# 00_POWER.net
KiCad netlist of a schematic drawn in Altium Designer
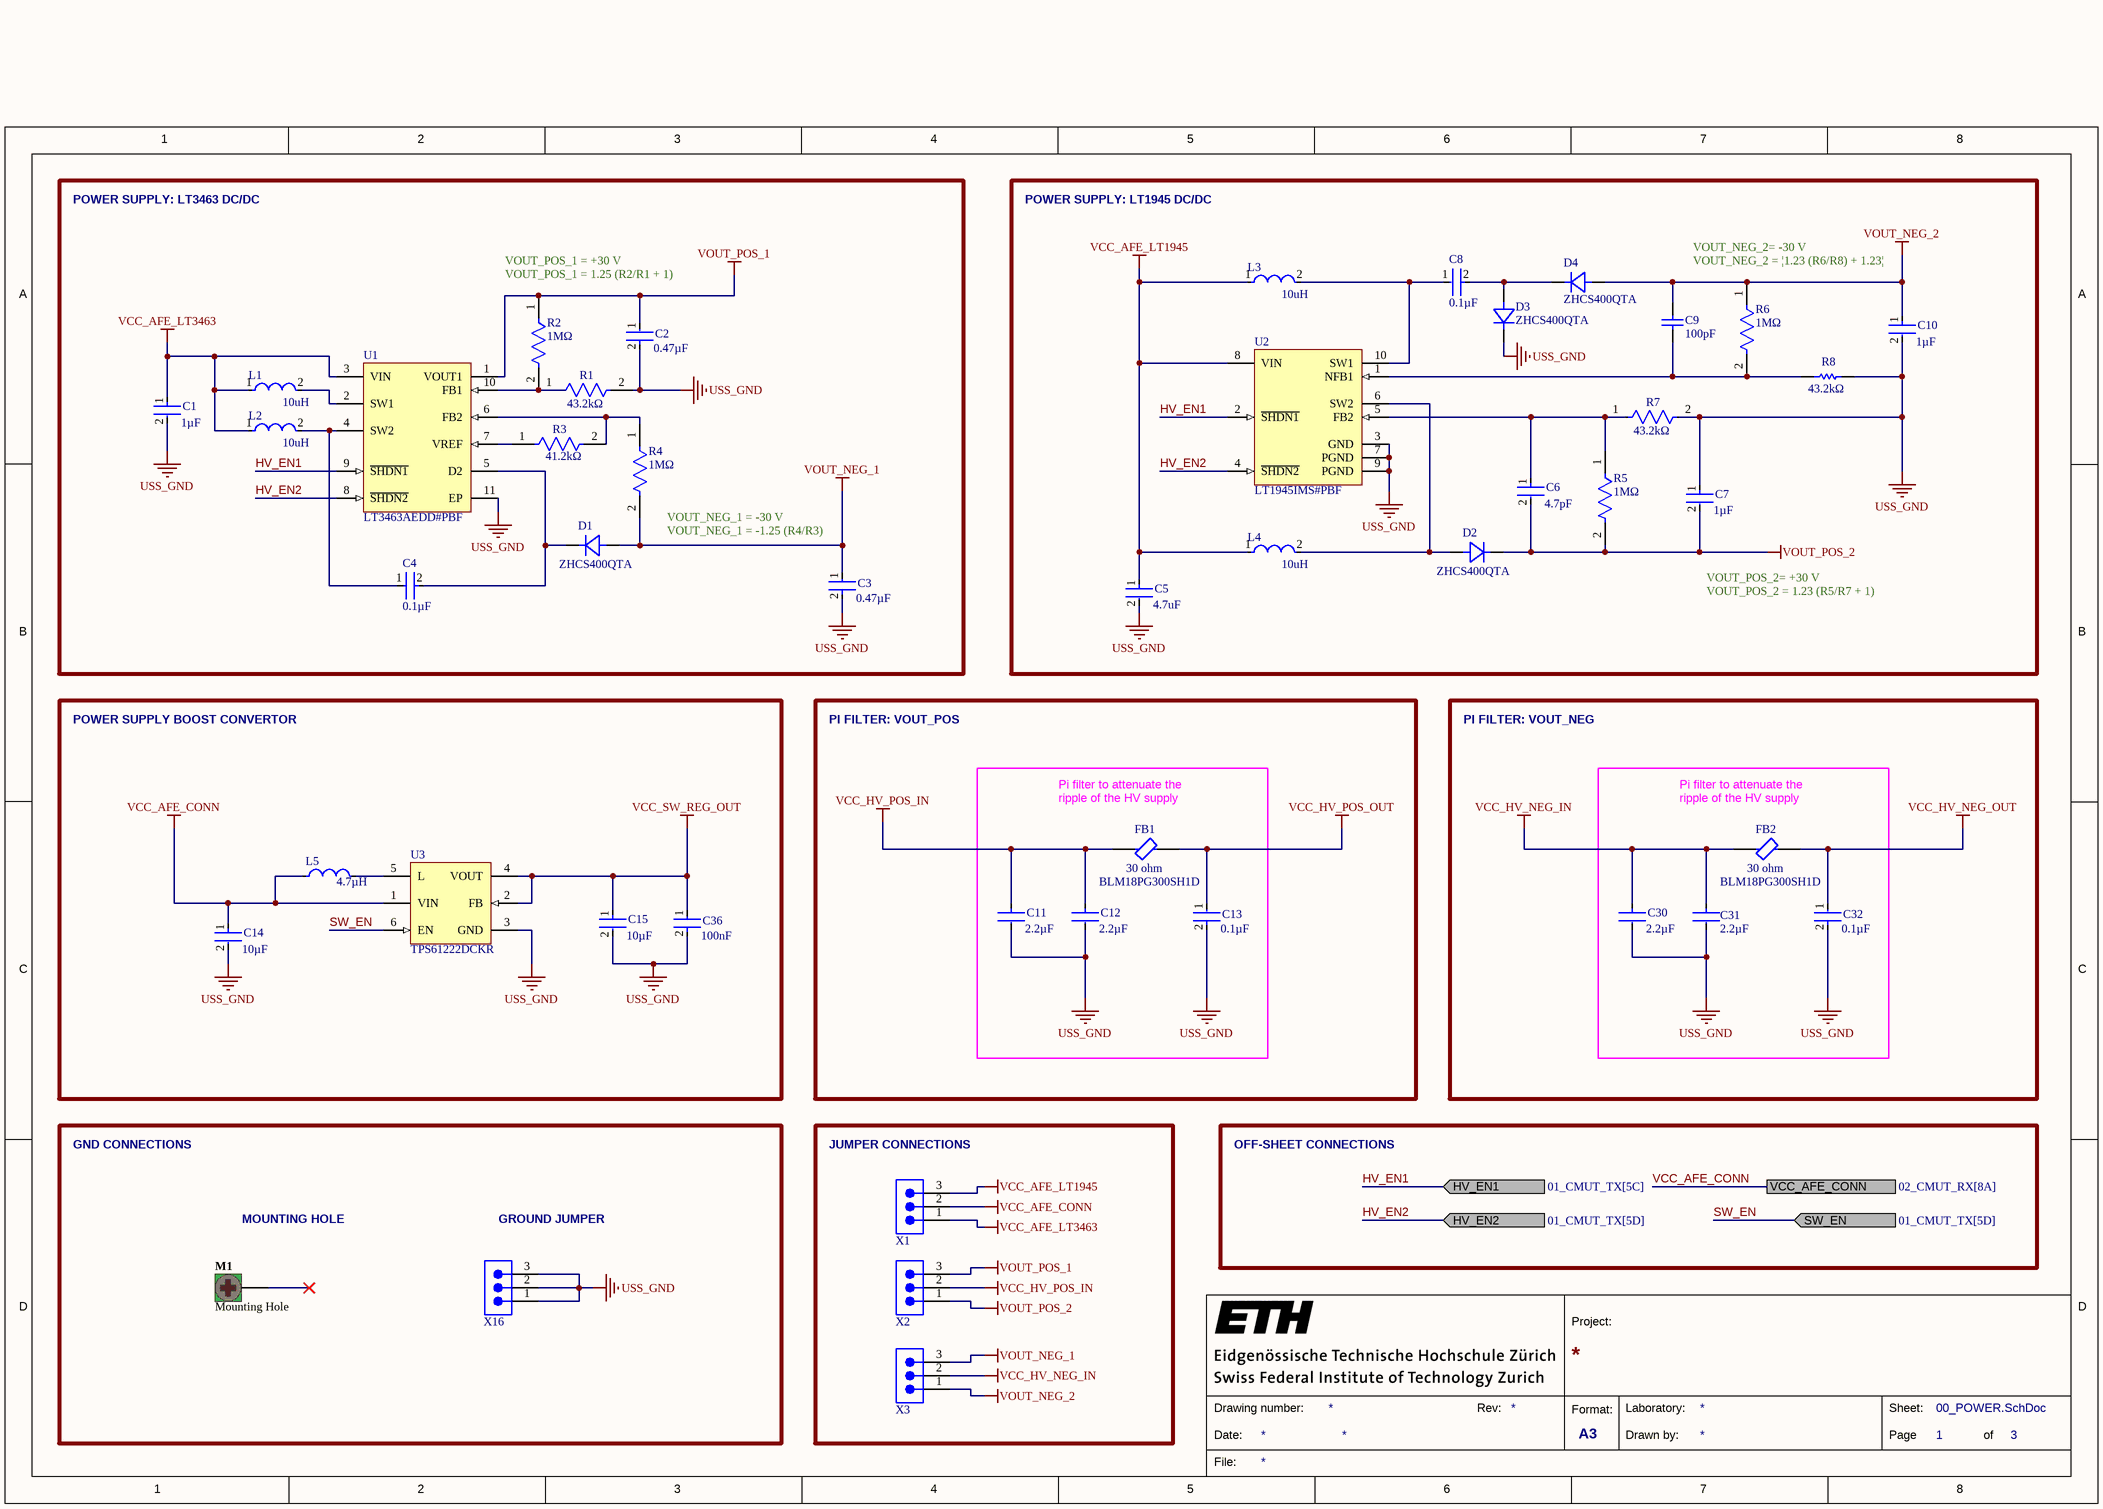
[diagram p0: 00_POWER.SchDoc]

(export (version "E")
  (design (tool "Eeschema 10.0.6"))
  (components
    (comp (ref "C1")
      (value "CGA3E3X5R1H105K")
      (footprint "FP-CGA3E-0_3-0_1-IPC_B")
      (description "Cap Ceramic 1uF 50V X5R 10% Pad SMD 0603 +85°C Automotive T/R")
      (fields (field (name "TOLERANCE") "10%") (field (name "CAPACITANCE") "1µF"))
      (libsource (lib "Altium Content Vault") (part "b4654b650e69147ec39a6b967a45e02"))
    )
    (comp (ref "C2")
      (value "C1608X5R1H474K080AB")
      (footprint "FP-C1608-080-0_1-IPC_C")
      (description "Multilayer Ceramic Capacitors 470nF ±10% 50V X5R SMD 0603")
      (fields
        (field (name "VOLTAGE") "50V")
        (field (name "TOLERANCE") "10%")
        (field (name "CAPACITANCE") "0.47µF")
      )
      (libsource (lib "Altium Content Vault") (part "236180d848d6139a670b325ea6854c9"))
    )
    (comp (ref "C3")
      (value "C1608X5R1H474K080AB")
      (footprint "FP-C1608-080-0_1-IPC_C")
      (description "Multilayer Ceramic Capacitors 470nF ±10% 50V X5R SMD 0603")
      (fields
        (field (name "VOLTAGE") "50V")
        (field (name "TOLERANCE") "10%")
        (field (name "CAPACITANCE") "0.47µF")
      )
      (libsource (lib "Altium Content Vault") (part "236180d848d6139a670b325ea6854c9"))
    )
    (comp (ref "C4")
      (value "C1608X5R1H104K080AA")
      (footprint "FP-C1608-080-0_1-MFG")
      (description "Multilayer Ceramic Capacitors 100nF ±10% 50V X5R SMD 0603")
      (fields (field (name "TOLERANCE") "10%") (field (name "CAPACITANCE") "0.1µF"))
      (libsource (lib "Altium Content Vault") (part "236180d848d6139a670b325ea6854c9"))
    )
    (comp (ref "C5")
      (value "C1608X5R1V475K080AC")
      (footprint "FP-C1608-080-0_2-MFG")
      (description "CAP CER 4.7UF 35V X5R 0603")
      (fields (field (name "CAPACITANCE") "4.7uF") (field (name "TOLERANCE") "10%"))
      (libsource (lib "Altium Content Vault") (part "02cd4be3c70576c341d710602a673aa"))
    )
    (comp (ref "C6")
      (value "C0603C479K5GAC7867")
      (footprint "FP-C0603C-CF-MFG")
      (description "CAP CER 4.7PF 50V NP0 0603")
      (fields
        (field (name "OCTOPART") "https://octopart.com/c0603c479k5gac7867-kemet-2009260")
        (field (name "MANUFACTURER") "KEMET")
        (field (name "CAPACITANCE") "4.7pF")
      )
      (libsource (lib "Altium Content Vault") (part "b4654b650e69147ec39a6b967a45e02"))
    )
    (comp (ref "C7")
      (value "CGA3E3X5R1H105K")
      (footprint "FP-CGA3E-0_3-0_1-IPC_B")
      (description "Cap Ceramic 1uF 50V X5R 10% Pad SMD 0603 +85°C Automotive T/R")
      (fields (field (name "TOLERANCE") "10%") (field (name "CAPACITANCE") "1µF"))
      (libsource (lib "Altium Content Vault") (part "b4654b650e69147ec39a6b967a45e02"))
    )
    (comp (ref "C8")
      (value "C1608X5R1H104K080AA")
      (footprint "FP-C1608-080-0_1-MFG")
      (description "Multilayer Ceramic Capacitors 100nF ±10% 50V X5R SMD 0603")
      (fields (field (name "TOLERANCE") "10%") (field (name "CAPACITANCE") "0.1µF"))
      (libsource (lib "Altium Content Vault") (part "236180d848d6139a670b325ea6854c9"))
    )
    (comp (ref "C9")
      (value "06035C101KAT2A")
      (footprint "CAPC1608X90X35LL15T15")
      (fields (field (name "MANUFACTURER") "AVX Interconnect / Elco") (field (name "CAPACITANCE") "100pF"))
      (libsource (lib "Altium Content Vault") (part "CAP"))
    )
    (comp (ref "C10")
      (value "CGA3E3X5R1H105K")
      (footprint "FP-CGA3E-0_3-0_1-IPC_B")
      (description "Cap Ceramic 1uF 50V X5R 10% Pad SMD 0603 +85°C Automotive T/R")
      (fields (field (name "TOLERANCE") "10%") (field (name "CAPACITANCE") "1µF"))
      (libsource (lib "Altium Content Vault") (part "b4654b650e69147ec39a6b967a45e02"))
    )
    (comp (ref "C11")
      (value "GRM188R61H225KE11D")
      (footprint "FP-GRM188-0_2-IPC_C")
      (description "Chip Multilayer Ceramic Capacitors for General Purpose, 0603, 2.2uF, X5R, 15%, 10%, 50V")
      (fields (field (name "TOLERANCE") "10%") (field (name "CAPACITANCE") "2.2µF"))
      (libsource (lib "Altium Content Vault") (part "11868f565c42a9108669ba33697ecf6"))
    )
    (comp (ref "C12")
      (value "GRM188R61H225KE11D")
      (footprint "FP-GRM188-0_2-IPC_C")
      (description "Chip Multilayer Ceramic Capacitors for General Purpose, 0603, 2.2uF, X5R, 15%, 10%, 50V")
      (fields (field (name "TOLERANCE") "10%") (field (name "CAPACITANCE") "2.2µF"))
      (libsource (lib "Altium Content Vault") (part "11868f565c42a9108669ba33697ecf6"))
    )
    (comp (ref "C13")
      (value "C1608X5R1H104K080AA")
      (footprint "FP-C1608-080-0_1-MFG")
      (description "Multilayer Ceramic Capacitors 100nF ±10% 50V X5R SMD 0603")
      (fields (field (name "TOLERANCE") "10%") (field (name "CAPACITANCE") "0.1µF"))
      (libsource (lib "Altium Content Vault") (part "236180d848d6139a670b325ea6854c9"))
    )
    (comp (ref "C14")
      (value "GRM188R6YA106MA73D")
      (footprint "FP-GRM188-0_2-IPC_C")
      (description "Chip Multilayer Ceramic Capacitors for General Purpose, 0603, 10uF, X5R, 15%, 20%, 35V")
      (fields (field (name "CAPACITANCE") "10µF") (field (name "TOLERANCE") "20%"))
      (libsource (lib "") (part "11868f565c42a9108669ba33697ecf6_1"))
    )
    (comp (ref "C15")
      (value "GRM188R6YA106MA73D")
      (footprint "FP-GRM188-0_2-IPC_C")
      (description "Chip Multilayer Ceramic Capacitors for General Purpose, 0603, 10uF, X5R, 15%, 20%, 35V")
      (fields (field (name "CAPACITANCE") "10µF") (field (name "TOLERANCE") "20%"))
      (libsource (lib "") (part "11868f565c42a9108669ba33697ecf6_1"))
    )
    (comp (ref "C30")
      (value "GRM188R61H225KE11D")
      (footprint "FP-GRM188-0_2-IPC_C")
      (description "Chip Multilayer Ceramic Capacitors for General Purpose, 0603, 2.2uF, X5R, 15%, 10%, 50V")
      (fields (field (name "TOLERANCE") "10%") (field (name "CAPACITANCE") "2.2µF"))
      (libsource (lib "Altium Content Vault") (part "11868f565c42a9108669ba33697ecf6"))
    )
    (comp (ref "C31")
      (value "Murata GRM188R61H225KE11D")
      (footprint "FP-GRM188-0_2-IPC_C")
      (description "Chip Multilayer Ceramic Capacitors for General Purpose, 0603, 2.2uF, X5R, 15%, 10%, 50V")
      (fields (field (name "TOLERANCE") "10%") (field (name "CAPACITANCE") "2.2µF"))
      (libsource (lib "Altium Content Vault") (part "11868f565c42a9108669ba33697ecf6"))
    )
    (comp (ref "C32")
      (value "C1608X5R1H104K080AA")
      (footprint "FP-C1608-080-0_1-MFG")
      (description "Multilayer Ceramic Capacitors 100nF ±10% 50V X5R SMD 0603")
      (fields (field (name "TOLERANCE") "10%") (field (name "CAPACITANCE") "0.1µF"))
      (libsource (lib "Altium Content Vault") (part "236180d848d6139a670b325ea6854c9"))
    )
    (comp (ref "C36")
      (value "C1608X5R1H104K080AA")
      (footprint "FP-C1608-080-0_1-MFG")
      (description "Multilayer Ceramic Capacitors 100nF ±10% 50V X5R SMD 0603")
      (fields (field (name "TOLERANCE") "10%") (field (name "CAPACITANCE") "100nF"))
      (libsource (lib "Altium Content Vault") (part "236180d848d6139a670b325ea6854c9"))
    )
    (comp (ref "D1")
      (value "ZHCS400QTA")
      (footprint "DIODE_SOD323_DIO")
      (description "Diode Schottky 40V 1A Automotive 2-Pin SOD-323 T/R")
      (fields (field (name "MANUFACTURER") "Diodes"))
      (libsource (lib "Schlib1") (part "ZHCS400QTA"))
    )
    (comp (ref "D2")
      (value "ZHCS400QTA")
      (footprint "DIODE_SOD323_DIO")
      (description "Diode Schottky 40V 1A Automotive 2-Pin SOD-323 T/R")
      (fields (field (name "MANUFACTURER") "Diodes"))
      (libsource (lib "Schlib1") (part "ZHCS400QTA"))
    )
    (comp (ref "D3")
      (value "ZHCS400QTA")
      (footprint "DIODE_SOD323_DIO")
      (description "Diode Schottky 40V 1A Automotive 2-Pin SOD-323 T/R")
      (fields (field (name "MANUFACTURER") "Diodes"))
      (libsource (lib "Schlib1") (part "ZHCS400QTA"))
    )
    (comp (ref "D4")
      (value "ZHCS400QTA")
      (footprint "DIODE_SOD323_DIO")
      (description "Diode Schottky 40V 1A Automotive 2-Pin SOD-323 T/R")
      (fields (field (name "MANUFACTURER") "Diodes"))
      (libsource (lib "Schlib1") (part "ZHCS400QTA"))
    )
    (comp (ref "FB1")
      (value "BLM18PG300SH1D")
      (footprint "FP-BLM18-0_15-t0_8-IPC_A")
      (description "Chip Ferrite Bead, 0603, 30Ω @ 100MHz, 0.05Ω, , 1A")
      (fields (field (name "IMPEDANCE") "30 ohm") (field (name "TOLERANCE") "25%"))
      (libsource (lib "Altium Content Vault") (part "5f30dd21d616792df468990f7003faa"))
    )
    (comp (ref "FB2")
      (value "BLM18PG300SH1D")
      (footprint "FP-BLM18-0_15-t0_8-IPC_A")
      (description "Chip Ferrite Bead, 0603, 30Ω @ 100MHz, 0.05Ω, , 1A")
      (fields (field (name "IMPEDANCE") "30 ohm") (field (name "TOLERANCE") "25%"))
      (libsource (lib "Altium Content Vault") (part "5f30dd21d616792df468990f7003faa"))
    )
    (comp (ref "L1")
      (value "B82422A1103K100")
      (footprint "FP-B82422A-MFG")
      (description "FIXED IND 10UH 180MA 1.6 OHM SMD")
      (fields (field (name "INDUCTANCE") "10uH") (field (name "TOLERANCE") "10%"))
      (libsource (lib "") (part "725321dda6339637d4d059423bc1c3c_1"))
    )
    (comp (ref "L2")
      (value "B82422A1103K100")
      (footprint "FP-B82422A-MFG")
      (description "FIXED IND 10UH 180MA 1.6 OHM SMD")
      (fields (field (name "INDUCTANCE") "10uH") (field (name "TOLERANCE") "10%"))
      (libsource (lib "") (part "725321dda6339637d4d059423bc1c3c_1"))
    )
    (comp (ref "L3")
      (value "B82422A1103K100")
      (footprint "FP-B82422A-MFG")
      (description "FIXED IND 10UH 180MA 1.6 OHM SMD")
      (fields (field (name "INDUCTANCE") "10uH") (field (name "TOLERANCE") "10%"))
      (libsource (lib "") (part "725321dda6339637d4d059423bc1c3c_1"))
    )
    (comp (ref "L4")
      (value "B82422A1103K100")
      (footprint "FP-B82422A-MFG")
      (description "FIXED IND 10UH 180MA 1.6 OHM SMD")
      (fields (field (name "INDUCTANCE") "10uH") (field (name "TOLERANCE") "10%"))
      (libsource (lib "") (part "725321dda6339637d4d059423bc1c3c_1"))
    )
    (comp (ref "L5")
      (value "NR3012T4R7M")
      (footprint "FP-NR3012-MFG")
      (description "SMD Power Inductors 4.7uH ±20% 0.77A 0.13Ω")
      (fields (field (name "TOLERANCE") "20%") (field (name "INDUCTANCE") "4.7µH"))
      (libsource (lib "Altium Content Vault") (part "725321dda6339637d4d059423bc1c3c"))
    )
    (comp (ref "M1")
      (value "Mounting Hole")
      (footprint "Mounting Hole")
      (description "M2 Hole, 2.4mm drill, 5mm landing pads, 3mm pad in middle layers, no overlay")
      (libsource (lib "ETHZ Vault") (part "Hole"))
    )
    (comp (ref "R1")
      (value "RC0603FR-0743K2L")
      (footprint "FP-RC0603-0_55-MFG")
      (description "RES SMD 43.2K OHM 1% 1/10W 0603")
      (fields (field (name "TOLERANCE") "1%") (field (name "RESISTANCE") "43.2kΩ"))
      (libsource (lib "Altium Content Vault") (part "1029c3af85768c4190bb7ad29bc67b5"))
    )
    (comp (ref "R2")
      (value "RC0603JR-071ML")
      (footprint "FP-RC0603-0_55-IPC_C")
      (description "RES SMD 1M OHM 5% 1/10W 0603")
      (fields (field (name "TOLERANCE") "5%") (field (name "RESISTANCE") "1MΩ"))
      (libsource (lib "Altium Content Vault") (part "1029c3af85768c4190bb7ad29bc67b5"))
    )
    (comp (ref "R3")
      (value "RK73H1JTTDD4122D")
      (footprint "FP-RK73H1J-IPC_A")
      (description "41.2kΩ ±0.5% 0.1W Chip Resistor 0603 Thick Film AEC-Q200 Qualified")
      (fields (field (name "RESISTANCE") "41.2kΩ") (field (name "TOLERANCE") "0.5%"))
      (libsource (lib "Altium Content Vault") (part "1029c3af85768c4190bb7ad29bc67b5"))
    )
    (comp (ref "R4")
      (value "RC0603JR-071ML")
      (footprint "FP-RC0603-0_55-IPC_C")
      (description "RES SMD 1M OHM 5% 1/10W 0603")
      (fields (field (name "TOLERANCE") "5%") (field (name "RESISTANCE") "1MΩ"))
      (libsource (lib "Altium Content Vault") (part "1029c3af85768c4190bb7ad29bc67b5"))
    )
    (comp (ref "R5")
      (value "RC0603JR-071ML")
      (footprint "FP-RC0603-0_55-IPC_C")
      (description "RES SMD 1M OHM 5% 1/10W 0603")
      (fields (field (name "TOLERANCE") "5%") (field (name "RESISTANCE") "1MΩ"))
      (libsource (lib "Altium Content Vault") (part "1029c3af85768c4190bb7ad29bc67b5"))
    )
    (comp (ref "R6")
      (value "RC0603JR-071ML")
      (footprint "FP-RC0603-0_55-IPC_C")
      (description "RES SMD 1M OHM 5% 1/10W 0603")
      (fields (field (name "TOLERANCE") "5%") (field (name "RESISTANCE") "1MΩ"))
      (libsource (lib "Altium Content Vault") (part "1029c3af85768c4190bb7ad29bc67b5"))
    )
    (comp (ref "R7")
      (value "RC0603FR-0743K2L")
      (footprint "FP-RC0603-0_55-MFG")
      (description "RES SMD 43.2K OHM 1% 1/10W 0603")
      (fields (field (name "TOLERANCE") "1%") (field (name "RESISTANCE") "43.2kΩ"))
      (libsource (lib "Altium Content Vault") (part "1029c3af85768c4190bb7ad29bc67b5"))
    )
    (comp (ref "R8")
      (value "RK73H1JTTD4322F")
      (footprint "RESC1608X55X30ML20T10")
      (fields (field (name "MANUFACTURER") "KOA Speer") (field (name "RESISTANCE") "43.2kΩ"))
      (libsource (lib "Altium Content Vault") (part "RES"))
    )
    (comp (ref "U1")
      (value "LT3463AEDD#PBF")
      (footprint "LT-DD-10_V")
      (fields (field (name "MANUFACTURER") "Linear Technology"))
      (libsource (lib "Altium Content Vault") (part "LT-LT3463A-DD-10"))
    )
    (comp (ref "U2")
      (value "LT1945IMS#PBF")
      (footprint "LT-MS-10_L")
      (fields (field (name "MANUFACTURER") "Linear Technology"))
      (libsource (lib "Altium Content Vault") (part "LT-LT1945-MS-10"))
    )
    (comp (ref "U3")
      (value "TPS61222DCKR")
      (footprint "DCK0006A_L")
      (fields (field (name "MANUFACTURER") "Texas Instruments"))
      (libsource (lib "Altium Content Vault") (part "TI-TPS61222DCK6"))
    )
    (comp (ref "X1")
      (value "68000-103HLF")
      (footprint "68000-103HLF")
      (description "3 Positions Header, Unshrouded Connector 0.100\" (2.54mm) Through Hole Gold or Gold, GXT™")
      (fields (field (name "MANUFACTURER") "Amphenol FCI"))
      (libsource (lib "ETHZ Vault") (part "CON-1x3-Male"))
    )
    (comp (ref "X2")
      (value "68000-103HLF")
      (footprint "68000-103HLF")
      (description "3 Positions Header, Unshrouded Connector 0.100\" (2.54mm) Through Hole Gold or Gold, GXT™")
      (fields (field (name "MANUFACTURER") "Amphenol FCI"))
      (libsource (lib "ETHZ Vault") (part "CON-1x3-Male"))
    )
    (comp (ref "X3")
      (value "68000-103HLF")
      (footprint "68000-103HLF")
      (description "3 Positions Header, Unshrouded Connector 0.100\" (2.54mm) Through Hole Gold or Gold, GXT™")
      (fields (field (name "MANUFACTURER") "Amphenol FCI"))
      (libsource (lib "ETHZ Vault") (part "CON-1x3-Male"))
    )
    (comp (ref "X16")
      (value "68000-103HLF")
      (footprint "68000-103HLF")
      (description "3 Positions Header, Unshrouded Connector 0.100\" (2.54mm) Through Hole Gold or Gold, GXT™")
      (fields (field (name "MANUFACTURER") "Amphenol FCI"))
      (libsource (lib "ETHZ Vault") (part "CON-1x3-Male"))
    )
  )
  (nets
    (net (code "1") (name "/HV_EN1") (class "Default")
      (node (ref "U1") (pin "9") (pinfunction "~{SHDN1}_9") (pintype "input"))
      (node (ref "U2") (pin "2") (pinfunction "~{SHDN1}_2") (pintype "input"))
    )
    (net (code "2") (name "/HV_EN2") (class "Default")
      (node (ref "U1") (pin "8") (pinfunction "~{SHDN2}_8") (pintype "input"))
      (node (ref "U2") (pin "4") (pinfunction "~{SHDN2}_4") (pintype "input"))
    )
    (net (code "3") (name "/SW_EN") (class "Default")
      (node (ref "U3") (pin "6") (pinfunction "EN_6") (pintype "input"))
    )
    (net (code "4") (name "Net-(C8-Pad2)") (class "Default")
      (node (ref "C8") (pin "2") (pinfunction "2_2") (pintype "passive"))
      (node (ref "D3") (pin "2") (pinfunction "2_2") (pintype "passive"))
      (node (ref "D4") (pin "1") (pinfunction "1_1") (pintype "passive"))
    )
    (net (code "5") (name "Net-(U1-D2)") (class "Default")
      (node (ref "C4") (pin "2") (pinfunction "2_2") (pintype "passive"))
      (node (ref "D1") (pin "1") (pinfunction "1_1") (pintype "passive"))
      (node (ref "U1") (pin "5") (pinfunction "D2_5") (pintype "passive"))
    )
    (net (code "6") (name "Net-(U1-FB1)") (class "Default")
      (node (ref "R1") (pin "1") (pinfunction "1_1") (pintype "passive"))
      (node (ref "R2") (pin "2") (pinfunction "2_2") (pintype "passive"))
      (node (ref "U1") (pin "10") (pinfunction "FB1_10") (pintype "input"))
    )
    (net (code "7") (name "Net-(U1-FB2)") (class "Default")
      (node (ref "R3") (pin "2") (pinfunction "2_2") (pintype "passive"))
      (node (ref "R4") (pin "1") (pinfunction "1_1") (pintype "passive"))
      (node (ref "U1") (pin "6") (pinfunction "FB2_6") (pintype "input"))
    )
    (net (code "8") (name "Net-(U1-SW1)") (class "Default")
      (node (ref "L1") (pin "2") (pinfunction "2_2") (pintype "passive"))
      (node (ref "U1") (pin "2") (pinfunction "SW1_2") (pintype "passive"))
    )
    (net (code "9") (name "Net-(U1-SW2)") (class "Default")
      (node (ref "C4") (pin "1") (pinfunction "1_1") (pintype "passive"))
      (node (ref "L2") (pin "2") (pinfunction "2_2") (pintype "passive"))
      (node (ref "U1") (pin "4") (pinfunction "SW2_4") (pintype "passive"))
    )
    (net (code "10") (name "Net-(U1-VREF)") (class "Default")
      (node (ref "R3") (pin "1") (pinfunction "1_1") (pintype "passive"))
      (node (ref "U1") (pin "7") (pinfunction "VREF_7") (pintype "input"))
    )
    (net (code "11") (name "Net-(U2-FB2)") (class "Default")
      (node (ref "C6") (pin "1") (pinfunction "1_1") (pintype "passive"))
      (node (ref "R5") (pin "1") (pinfunction "1_1") (pintype "passive"))
      (node (ref "R7") (pin "1") (pinfunction "1_1") (pintype "passive"))
      (node (ref "U2") (pin "5") (pinfunction "FB2_5") (pintype "input"))
    )
    (net (code "12") (name "Net-(U2-NFB1)") (class "Default")
      (node (ref "C9") (pin "1") (pinfunction "1_1") (pintype "passive"))
      (node (ref "R6") (pin "2") (pinfunction "2_2") (pintype "passive"))
      (node (ref "R8") (pin "1") (pinfunction "1_1") (pintype "passive"))
      (node (ref "U2") (pin "1") (pinfunction "NFB1_1") (pintype "input"))
    )
    (net (code "13") (name "Net-(U2-SW1)") (class "Default")
      (node (ref "C8") (pin "1") (pinfunction "1_1") (pintype "passive"))
      (node (ref "L3") (pin "2") (pinfunction "2_2") (pintype "passive"))
      (node (ref "U2") (pin "10") (pinfunction "SW1_10") (pintype "power_in"))
    )
    (net (code "14") (name "Net-(U2-SW2)") (class "Default")
      (node (ref "D2") (pin "2") (pinfunction "2_2") (pintype "passive"))
      (node (ref "L4") (pin "2") (pinfunction "2_2") (pintype "passive"))
      (node (ref "U2") (pin "6") (pinfunction "SW2_6") (pintype "power_in"))
    )
    (net (code "15") (name "Net-(U3-L)") (class "Default")
      (node (ref "L5") (pin "2") (pinfunction "2_2") (pintype "passive"))
      (node (ref "U3") (pin "5") (pinfunction "L_5") (pintype "power_in"))
    )
    (net (code "16") (name "USS_GND") (class "Default")
      (node (ref "C1") (pin "2") (pinfunction "2_2") (pintype "passive"))
      (node (ref "C10") (pin "2") (pinfunction "2_2") (pintype "passive"))
      (node (ref "C11") (pin "2") (pinfunction "2_2") (pintype "passive"))
      (node (ref "C12") (pin "2") (pinfunction "2_2") (pintype "passive"))
      (node (ref "C13") (pin "2") (pinfunction "2_2") (pintype "passive"))
      (node (ref "C14") (pin "2") (pinfunction "2_2") (pintype "passive"))
      (node (ref "C15") (pin "2") (pinfunction "2_2") (pintype "passive"))
      (node (ref "C2") (pin "2") (pinfunction "2_2") (pintype "passive"))
      (node (ref "C3") (pin "2") (pinfunction "2_2") (pintype "passive"))
      (node (ref "C30") (pin "2") (pinfunction "2_2") (pintype "passive"))
      (node (ref "C31") (pin "2") (pinfunction "2_2") (pintype "passive"))
      (node (ref "C32") (pin "2") (pinfunction "2_2") (pintype "passive"))
      (node (ref "C36") (pin "2") (pinfunction "2_2") (pintype "passive"))
      (node (ref "C5") (pin "2") (pinfunction "2_2") (pintype "passive"))
      (node (ref "C7") (pin "1") (pinfunction "1_1") (pintype "passive"))
      (node (ref "D3") (pin "1") (pinfunction "1_1") (pintype "passive"))
      (node (ref "R1") (pin "2") (pinfunction "2_2") (pintype "passive"))
      (node (ref "R7") (pin "2") (pinfunction "2_2") (pintype "passive"))
      (node (ref "R8") (pin "2") (pinfunction "2_2") (pintype "passive"))
      (node (ref "U1") (pin "11") (pinfunction "EP_11") (pintype "power_in"))
      (node (ref "U2") (pin "3") (pinfunction "GND_3") (pintype "power_in"))
      (node (ref "U2") (pin "7") (pinfunction "PGND_7") (pintype "power_in"))
      (node (ref "U2") (pin "9") (pinfunction "PGND_9") (pintype "power_in"))
      (node (ref "U3") (pin "3") (pinfunction "GND_3") (pintype "power_in"))
      (node (ref "X16") (pin "1") (pinfunction "1_1") (pintype "passive"))
      (node (ref "X16") (pin "2") (pinfunction "2_2") (pintype "passive"))
      (node (ref "X16") (pin "3") (pinfunction "3_3") (pintype "passive"))
    )
    (net (code "17") (name "VCC_AFE_CONN") (class "Default")
      (node (ref "C14") (pin "1") (pinfunction "1_1") (pintype "passive"))
      (node (ref "L5") (pin "1") (pinfunction "1_1") (pintype "passive"))
      (node (ref "U3") (pin "1") (pinfunction "VIN_1") (pintype "power_in"))
      (node (ref "X1") (pin "2") (pinfunction "2_2") (pintype "passive"))
    )
    (net (code "18") (name "VCC_AFE_LT1945") (class "Default")
      (node (ref "C5") (pin "1") (pinfunction "1_1") (pintype "passive"))
      (node (ref "L3") (pin "1") (pinfunction "1_1") (pintype "passive"))
      (node (ref "L4") (pin "1") (pinfunction "1_1") (pintype "passive"))
      (node (ref "U2") (pin "8") (pinfunction "VIN_8") (pintype "power_in"))
      (node (ref "X1") (pin "3") (pinfunction "3_3") (pintype "passive"))
    )
    (net (code "19") (name "VCC_AFE_LT3463") (class "Default")
      (node (ref "C1") (pin "1") (pinfunction "1_1") (pintype "passive"))
      (node (ref "L1") (pin "1") (pinfunction "1_1") (pintype "passive"))
      (node (ref "L2") (pin "1") (pinfunction "1_1") (pintype "passive"))
      (node (ref "U1") (pin "3") (pinfunction "VIN_3") (pintype "power_in"))
      (node (ref "X1") (pin "1") (pinfunction "1_1") (pintype "passive"))
    )
    (net (code "20") (name "VCC_HV_NEG_IN") (class "Default")
      (node (ref "C30") (pin "1") (pinfunction "1_1") (pintype "passive"))
      (node (ref "C31") (pin "1") (pinfunction "1_1") (pintype "passive"))
      (node (ref "FB2") (pin "1") (pinfunction "1_1") (pintype "passive"))
      (node (ref "X3") (pin "2") (pinfunction "2_2") (pintype "passive"))
    )
    (net (code "21") (name "VCC_HV_NEG_OUT") (class "Default")
      (node (ref "C32") (pin "1") (pinfunction "1_1") (pintype "passive"))
      (node (ref "FB2") (pin "2") (pinfunction "2_2") (pintype "passive"))
    )
    (net (code "22") (name "VCC_HV_POS_IN") (class "Default")
      (node (ref "C11") (pin "1") (pinfunction "1_1") (pintype "passive"))
      (node (ref "C12") (pin "1") (pinfunction "1_1") (pintype "passive"))
      (node (ref "FB1") (pin "1") (pinfunction "1_1") (pintype "passive"))
      (node (ref "X2") (pin "2") (pinfunction "2_2") (pintype "passive"))
    )
    (net (code "23") (name "VCC_HV_POS_OUT") (class "Default")
      (node (ref "C13") (pin "1") (pinfunction "1_1") (pintype "passive"))
      (node (ref "FB1") (pin "2") (pinfunction "2_2") (pintype "passive"))
    )
    (net (code "24") (name "VCC_SW_REG_OUT") (class "Default")
      (node (ref "C15") (pin "1") (pinfunction "1_1") (pintype "passive"))
      (node (ref "C36") (pin "1") (pinfunction "1_1") (pintype "passive"))
      (node (ref "U3") (pin "2") (pinfunction "FB_2") (pintype "input"))
      (node (ref "U3") (pin "4") (pinfunction "VOUT_4") (pintype "power_in"))
    )
    (net (code "25") (name "VOUT_NEG_1") (class "Default")
      (node (ref "C3") (pin "1") (pinfunction "1_1") (pintype "passive"))
      (node (ref "D1") (pin "2") (pinfunction "2_2") (pintype "passive"))
      (node (ref "R4") (pin "2") (pinfunction "2_2") (pintype "passive"))
      (node (ref "X3") (pin "3") (pinfunction "3_3") (pintype "passive"))
    )
    (net (code "26") (name "VOUT_NEG_2") (class "Default")
      (node (ref "C10") (pin "1") (pinfunction "1_1") (pintype "passive"))
      (node (ref "C9") (pin "2") (pinfunction "2_2") (pintype "passive"))
      (node (ref "D4") (pin "2") (pinfunction "2_2") (pintype "passive"))
      (node (ref "R6") (pin "1") (pinfunction "1_1") (pintype "passive"))
      (node (ref "X3") (pin "1") (pinfunction "1_1") (pintype "passive"))
    )
    (net (code "27") (name "VOUT_POS_1") (class "Default")
      (node (ref "C2") (pin "1") (pinfunction "1_1") (pintype "passive"))
      (node (ref "R2") (pin "1") (pinfunction "1_1") (pintype "passive"))
      (node (ref "U1") (pin "1") (pinfunction "VOUT1_1") (pintype "power_in"))
      (node (ref "X2") (pin "3") (pinfunction "3_3") (pintype "passive"))
    )
    (net (code "28") (name "VOUT_POS_2") (class "Default")
      (node (ref "C6") (pin "2") (pinfunction "2_2") (pintype "passive"))
      (node (ref "C7") (pin "2") (pinfunction "2_2") (pintype "passive"))
      (node (ref "D2") (pin "1") (pinfunction "1_1") (pintype "passive"))
      (node (ref "R5") (pin "2") (pinfunction "2_2") (pintype "passive"))
      (node (ref "X2") (pin "1") (pinfunction "1_1") (pintype "passive"))
    )
    (net (code "29") (name "unconnected-(M1-Pad1)") (class "Default")
      (node (ref "M1") (pin "1") (pinfunction "1_1") (pintype "passive+no_connect"))
    )
  )
)
